# screen.net
KiCad netlist of a schematic drawn in Altium Designer
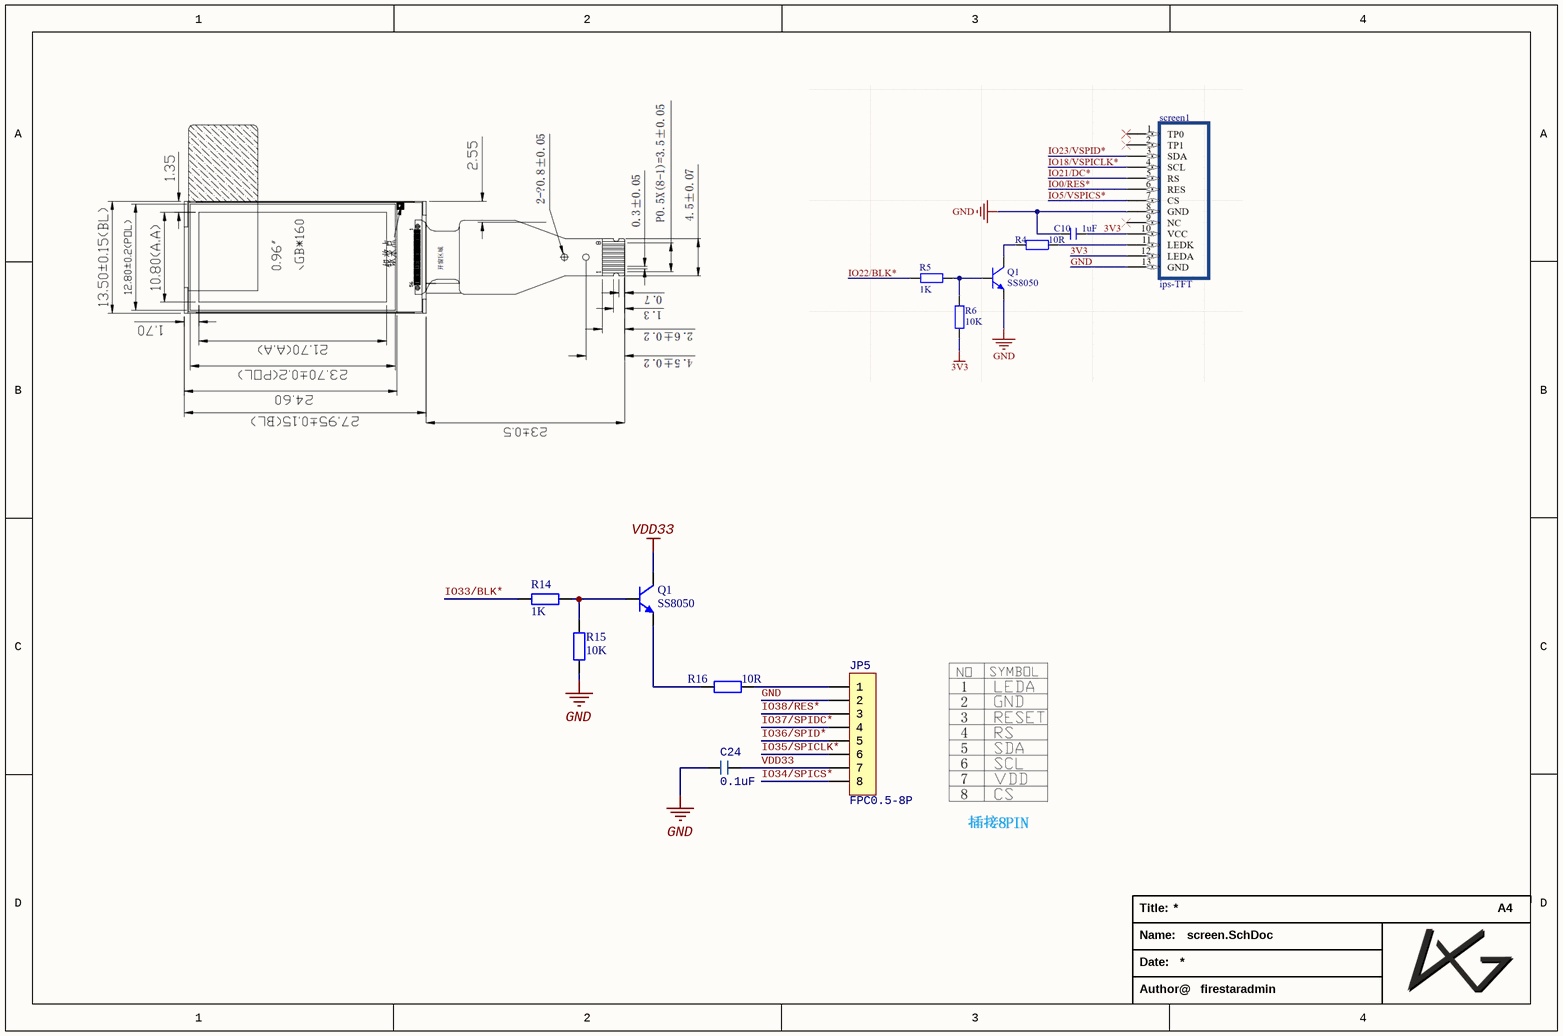
[diagram p0: screen.SchDoc]

(export (version "E")
  (design (tool "Eeschema 10.0.6"))
  (components
    (comp (ref "C24")
      (value "0.1uF")
      (footprint "C 0603_L")
      (description "无极性贴片电容")
      (fields (field (name "版权归属") "源创客"))
      (libsource (lib "SCH-电阻-电容-电感") (part "C"))
    )
    (comp (ref "JP5")
      (value "FPC0.5-8P")
      (footprint "FPC0.5 2H-WS-8P")
      (description "FPC连接器")
      (fields (field (name "版权归属") "源创客"))
      (libsource (lib "SCH-接插件-FPC") (part "FPC-8P"))
    )
    (comp (ref "Q1")
      (value "SS8050")
      (footprint "SOT23-3L")
      (description "高频放大-NPN型")
      (fields (field (name "版权归属") "源创客"))
      (libsource (lib "SCH-三极管") (part "8050-SMD"))
    )
    (comp (ref "R14")
      (value "1K")
      (footprint "R 0603_L")
      (description "贴片电阻")
      (fields (field (name "版权归属") "源创客"))
      (libsource (lib "SCH-电阻-电容-电感") (part "R"))
    )
    (comp (ref "R15")
      (value "10K")
      (footprint "R 0603_L")
      (description "贴片电阻")
      (fields (field (name "版权归属") "源创客"))
      (libsource (lib "SCH-电阻-电容-电感") (part "R"))
    )
    (comp (ref "R16")
      (value "10R")
      (footprint "R 0603_L")
      (description "贴片电阻")
      (fields (field (name "版权归属") "源创客"))
      (libsource (lib "SCH-电阻-电容-电感") (part "R"))
    )
  )
  (nets
    (net (code "1") (name "/IO33{slash}BLK*") (class "Default")
      (node (ref "R14") (pin "2") (pinfunction "2_2") (pintype "passive"))
    )
    (net (code "2") (name "/IO34{slash}SPICS*") (class "Default")
      (node (ref "JP5") (pin "8") (pinfunction "8_8") (pintype "passive"))
    )
    (net (code "3") (name "/IO35{slash}SPICLK*") (class "Default")
      (node (ref "JP5") (pin "6") (pinfunction "6_6") (pintype "passive"))
    )
    (net (code "4") (name "/IO36{slash}SPID*") (class "Default")
      (node (ref "JP5") (pin "5") (pinfunction "5_5") (pintype "passive"))
    )
    (net (code "5") (name "/IO37{slash}SPIDC*") (class "Default")
      (node (ref "JP5") (pin "4") (pinfunction "4_4") (pintype "passive"))
    )
    (net (code "6") (name "/IO38{slash}RES*") (class "Default")
      (node (ref "JP5") (pin "3") (pinfunction "3_3") (pintype "passive"))
    )
    (net (code "7") (name "GND") (class "Default")
      (node (ref "C24") (pin "1") (pinfunction "1_1") (pintype "passive"))
      (node (ref "JP5") (pin "2") (pinfunction "2_2") (pintype "passive"))
      (node (ref "R15") (pin "1") (pinfunction "1_1") (pintype "passive"))
    )
    (net (code "8") (name "Net-(JP5-Pad1)") (class "Default")
      (node (ref "JP5") (pin "1") (pinfunction "1_1") (pintype "passive"))
      (node (ref "R16") (pin "1") (pinfunction "1_1") (pintype "passive"))
    )
    (net (code "9") (name "Net-(Q1-B)") (class "Default")
      (node (ref "Q1") (pin "1") (pinfunction "B_1") (pintype "passive"))
      (node (ref "R14") (pin "1") (pinfunction "1_1") (pintype "passive"))
      (node (ref "R15") (pin "2") (pinfunction "2_2") (pintype "passive"))
    )
    (net (code "10") (name "Net-(Q1-E)") (class "Default")
      (node (ref "Q1") (pin "2") (pinfunction "E_2") (pintype "passive"))
      (node (ref "R16") (pin "2") (pinfunction "2_2") (pintype "passive"))
    )
    (net (code "11") (name "VDD33") (class "Default")
      (node (ref "C24") (pin "2") (pinfunction "2_2") (pintype "passive"))
      (node (ref "JP5") (pin "7") (pinfunction "7_7") (pintype "passive"))
      (node (ref "Q1") (pin "3") (pinfunction "C_3") (pintype "passive"))
    )
  )
)
